# 20-12-2020-10pm.net
KiCad netlist of a schematic drawn in EAGLE
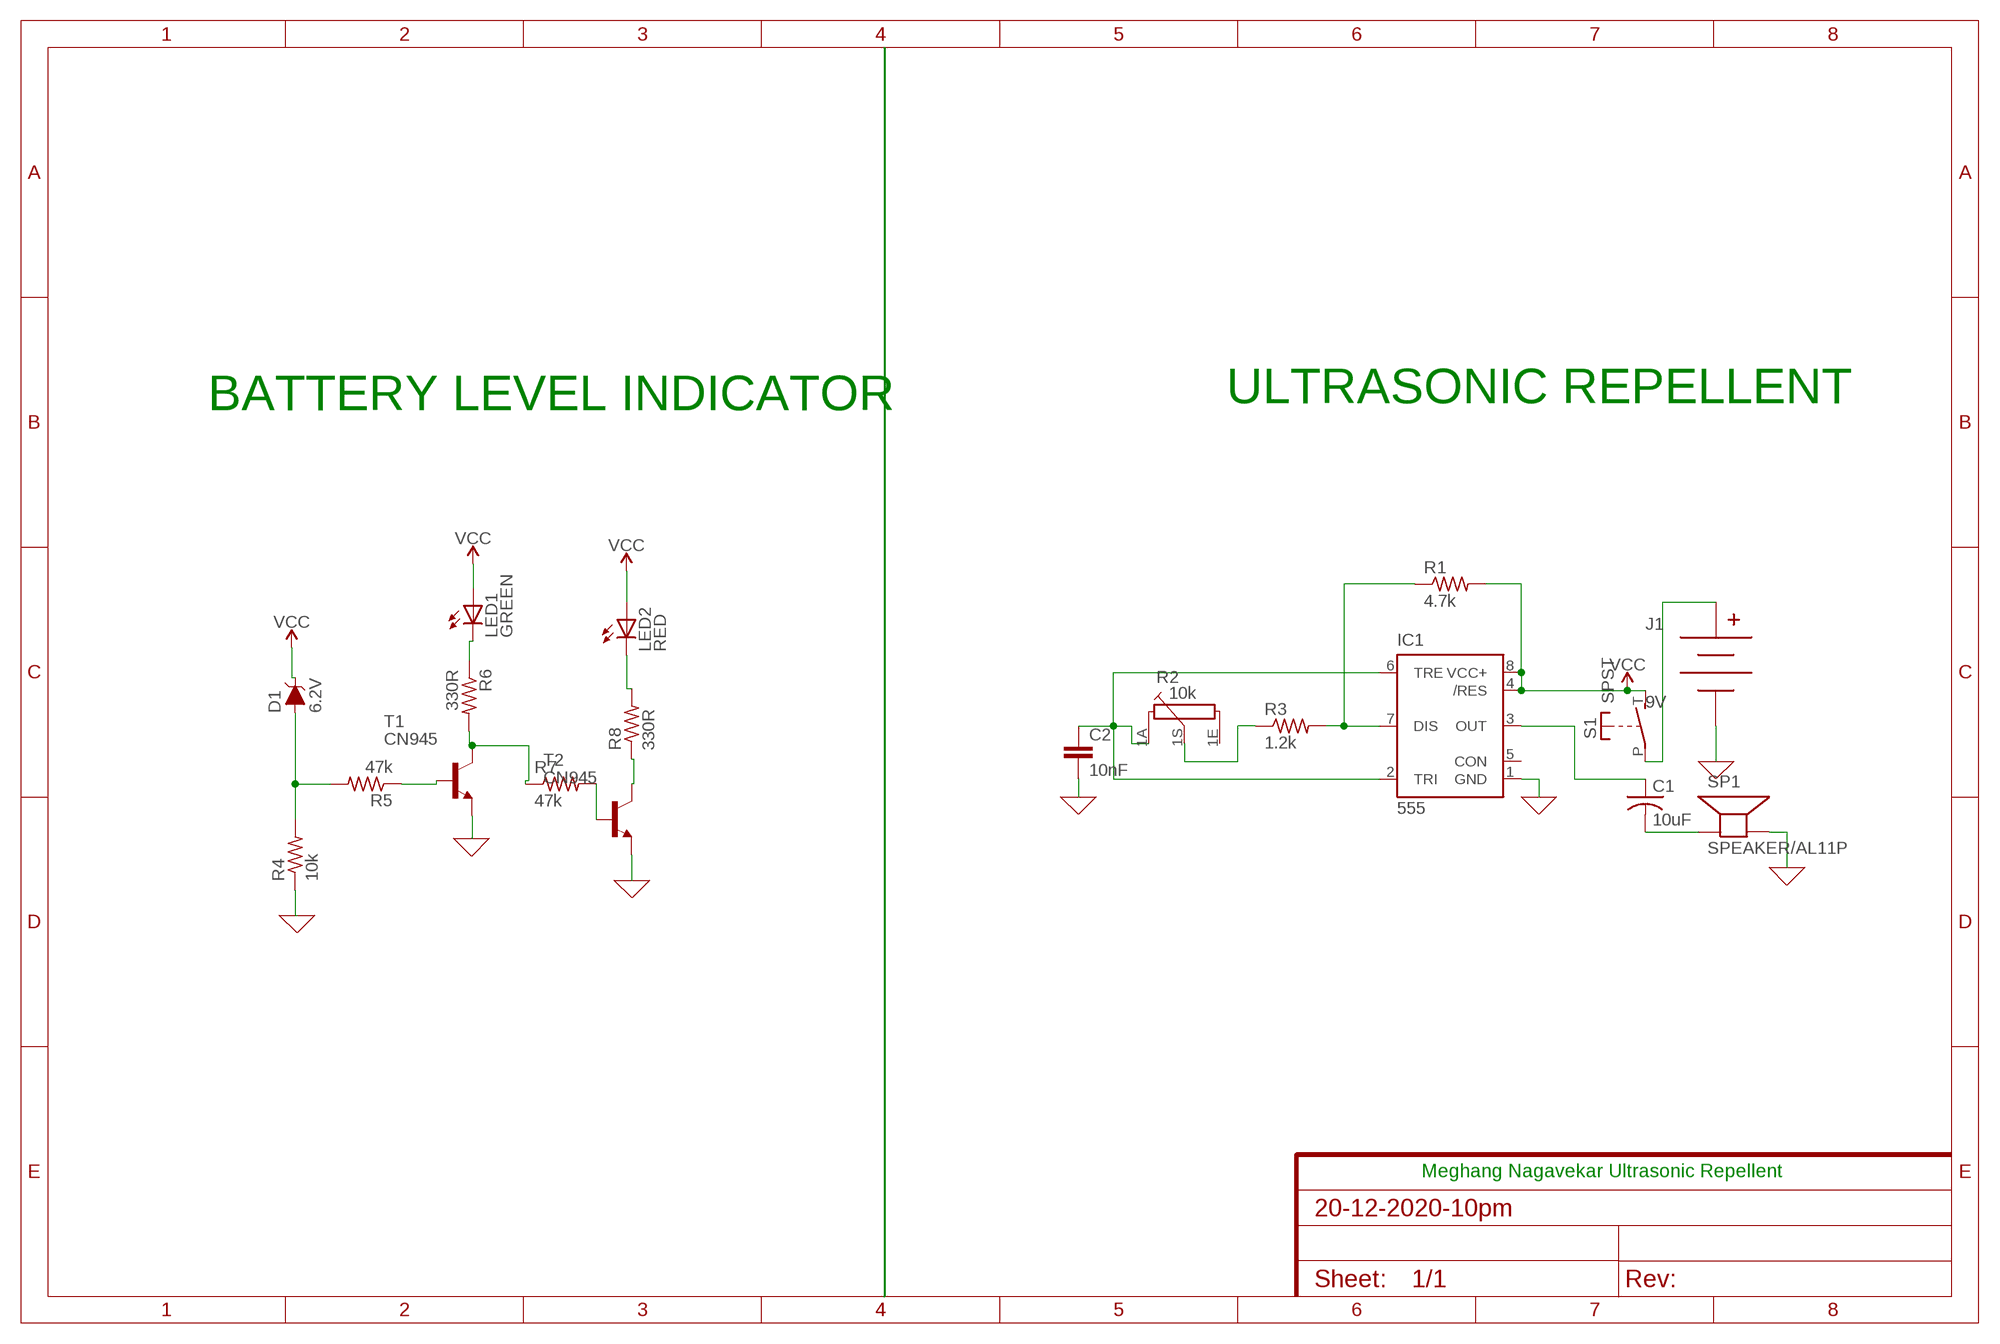
[diagram p0: schematic, sheet 1]

(export (version "E")
  (design (tool "Eeschema 10.0.6"))
  (components
    (comp (ref "C1")
      (value "10uF")
      (footprint "eagle-import:C0805")
      (libsource (lib "eagle-import") (part "C-USC0805"))
    )
    (comp (ref "C2")
      (value "10nF")
      (footprint "eagle-import:0603")
      (libsource (lib "eagle-import") (part "10NF-0603-50V-10%"))
    )
    (comp (ref "D1")
      (value "6.2V")
      (footprint "eagle-import:SOD-323")
      (libsource (lib "eagle-import") (part "DIODE-ZENER-BZT52C3V6S"))
    )
    (comp (ref "IC1")
      (value "555")
      (footprint "eagle-import:SO08")
      (libsource (lib "eagle-import") (part "555D"))
    )
    (comp (ref "J1")
      (value "9V")
      (footprint "eagle-import:BC9VPC")
      (libsource (lib "eagle-import") (part "BC9VPC"))
    )
    (comp (ref "LED1")
      (value "GREEN")
      (footprint "eagle-import:LED5MM")
      (libsource (lib "eagle-import") (part "LED5MM"))
    )
    (comp (ref "LED2")
      (value "RED")
      (footprint "eagle-import:LED5MM")
      (libsource (lib "eagle-import") (part "LED5MM"))
    )
    (comp (ref "R1")
      (value "4.7k")
      (footprint "eagle-import:R0805")
      (libsource (lib "eagle-import") (part "R-US_R0805"))
    )
    (comp (ref "R2")
      (value "10k")
      (footprint "eagle-import:PC16S")
      (libsource (lib "eagle-import") (part "PC16S"))
    )
    (comp (ref "R3")
      (value "1.2k")
      (footprint "eagle-import:R0805")
      (libsource (lib "eagle-import") (part "R-US_R0805"))
    )
    (comp (ref "R4")
      (value "10k")
      (footprint "eagle-import:R0805")
      (libsource (lib "eagle-import") (part "R-US_R0805"))
    )
    (comp (ref "R5")
      (value "47k")
      (footprint "eagle-import:R0805")
      (libsource (lib "eagle-import") (part "R-US_R0805"))
    )
    (comp (ref "R6")
      (value "330R")
      (footprint "eagle-import:R0805")
      (libsource (lib "eagle-import") (part "R-US_R0805"))
    )
    (comp (ref "R7")
      (value "47k")
      (footprint "eagle-import:R0805")
      (libsource (lib "eagle-import") (part "R-US_R0805"))
    )
    (comp (ref "R8")
      (value "330R")
      (footprint "eagle-import:R0805")
      (libsource (lib "eagle-import") (part "R-US_R0805"))
    )
    (comp (ref "S1")
      (value "SPST")
      (footprint "eagle-import:JUDCOSPST")
      (libsource (lib "eagle-import") (part "SPST"))
    )
    (comp (ref "SP1")
      (value "SPEAKER/AL11P")
      (footprint "eagle-import:AL11P")
      (libsource (lib "eagle-import") (part "SPEAKER/AL11P"))
    )
    (comp (ref "T1")
      (value "CN945")
      (footprint "eagle-import:TO92-EBC-OVAL")
      (libsource (lib "eagle-import") (part "2N2222"))
    )
    (comp (ref "T2")
      (value "CN945")
      (footprint "eagle-import:TO92-EBC-OVAL")
      (libsource (lib "eagle-import") (part "2N2222"))
    )
  )
  (nets
    (net (code "1") (name "GND") (class "Default")
      (node (ref "C2") (pin "2") (pinfunction "2_2") (pintype "passive"))
      (node (ref "IC1") (pin "1") (pinfunction "GND_1") (pintype "power_in"))
      (node (ref "J1") (pin "V-") (pinfunction "V-_V-") (pintype "bidirectional"))
      (node (ref "R4") (pin "1") (pinfunction "1_1") (pintype "passive"))
      (node (ref "SP1") (pin "-") (pinfunction "-_-") (pintype "passive"))
      (node (ref "T1") (pin "E") (pinfunction "E_E") (pintype "passive"))
      (node (ref "T2") (pin "E") (pinfunction "E_E") (pintype "passive"))
    )
    (net (code "2") (name "Net-(C1-Pad2)") (class "Default")
      (node (ref "C1") (pin "2") (pinfunction "2_2") (pintype "passive"))
      (node (ref "SP1") (pin "+") (pinfunction "+_+") (pintype "passive"))
    )
    (net (code "3") (name "Net-(D1-PadA)") (class "Default")
      (node (ref "D1") (pin "A") (pinfunction "A_A") (pintype "passive"))
      (node (ref "R4") (pin "2") (pinfunction "2_2") (pintype "passive"))
      (node (ref "R5") (pin "2") (pinfunction "2_2") (pintype "passive"))
    )
    (net (code "4") (name "Net-(IC1-DIS)") (class "Default")
      (node (ref "IC1") (pin "7") (pinfunction "DIS_7") (pintype "input"))
      (node (ref "R1") (pin "1") (pinfunction "1_1") (pintype "passive"))
      (node (ref "R3") (pin "2") (pinfunction "2_2") (pintype "passive"))
    )
    (net (code "5") (name "Net-(IC1-OUT)") (class "Default")
      (node (ref "C1") (pin "1") (pinfunction "1_1") (pintype "passive"))
      (node (ref "IC1") (pin "3") (pinfunction "OUT_3") (pintype "output"))
    )
    (net (code "6") (name "Net-(IC1-TRE)") (class "Default")
      (node (ref "C2") (pin "1") (pinfunction "1_1") (pintype "passive"))
      (node (ref "IC1") (pin "2") (pinfunction "TRI_2") (pintype "input"))
      (node (ref "IC1") (pin "6") (pinfunction "TRE_6") (pintype "input"))
      (node (ref "R2") (pin "1A") (pinfunction "1A_1A") (pintype "passive"))
    )
    (net (code "7") (name "Net-(J1-PadV+)") (class "Default")
      (node (ref "J1") (pin "V+") (pinfunction "V+_V+") (pintype "bidirectional"))
      (node (ref "S1") (pin "P") (pinfunction "P_P") (pintype "passive"))
    )
    (net (code "8") (name "Net-(LED1-C)") (class "Default")
      (node (ref "LED1") (pin "K") (pinfunction "C_K") (pintype "passive"))
      (node (ref "R6") (pin "1") (pinfunction "1_1") (pintype "passive"))
    )
    (net (code "9") (name "Net-(LED2-C)") (class "Default")
      (node (ref "LED2") (pin "K") (pinfunction "C_K") (pintype "passive"))
      (node (ref "R8") (pin "2") (pinfunction "2_2") (pintype "passive"))
    )
    (net (code "10") (name "Net-(R2-Pad1S)") (class "Default")
      (node (ref "R2") (pin "1S") (pinfunction "1S_1S") (pintype "passive"))
      (node (ref "R3") (pin "1") (pinfunction "1_1") (pintype "passive"))
    )
    (net (code "11") (name "Net-(R5-Pad1)") (class "Default")
      (node (ref "R5") (pin "1") (pinfunction "1_1") (pintype "passive"))
      (node (ref "T1") (pin "B") (pinfunction "B_B") (pintype "passive"))
    )
    (net (code "12") (name "Net-(R6-Pad2)") (class "Default")
      (node (ref "R6") (pin "2") (pinfunction "2_2") (pintype "passive"))
      (node (ref "R7") (pin "1") (pinfunction "1_1") (pintype "passive"))
      (node (ref "T1") (pin "C") (pinfunction "C_C") (pintype "passive"))
    )
    (net (code "13") (name "Net-(R7-Pad2)") (class "Default")
      (node (ref "R7") (pin "2") (pinfunction "2_2") (pintype "passive"))
      (node (ref "T2") (pin "B") (pinfunction "B_B") (pintype "passive"))
    )
    (net (code "14") (name "Net-(R8-Pad1)") (class "Default")
      (node (ref "R8") (pin "1") (pinfunction "1_1") (pintype "passive"))
      (node (ref "T2") (pin "C") (pinfunction "C_C") (pintype "passive"))
    )
    (net (code "15") (name "VCC") (class "Default")
      (node (ref "D1") (pin "C") (pinfunction "C_C") (pintype "passive"))
      (node (ref "IC1") (pin "4") (pinfunction "/RES_4") (pintype "input"))
      (node (ref "IC1") (pin "8") (pinfunction "VCC+_8") (pintype "power_in"))
      (node (ref "LED1") (pin "A") (pinfunction "A_A") (pintype "passive"))
      (node (ref "LED2") (pin "A") (pinfunction "A_A") (pintype "passive"))
      (node (ref "R1") (pin "2") (pinfunction "2_2") (pintype "passive"))
      (node (ref "S1") (pin "T") (pinfunction "S_T") (pintype "passive"))
    )
    (net (code "16") (name "unconnected-(IC1-CON-Pad5)") (class "Default")
      (node (ref "IC1") (pin "5") (pinfunction "CON_5") (pintype "input"))
    )
    (net (code "17") (name "unconnected-(R2-Pad1E)") (class "Default")
      (node (ref "R2") (pin "1E") (pinfunction "1E_1E") (pintype "passive"))
    )
  )
)
